# 8335-breakout.net
KiCad netlist of a schematic drawn in EAGLE
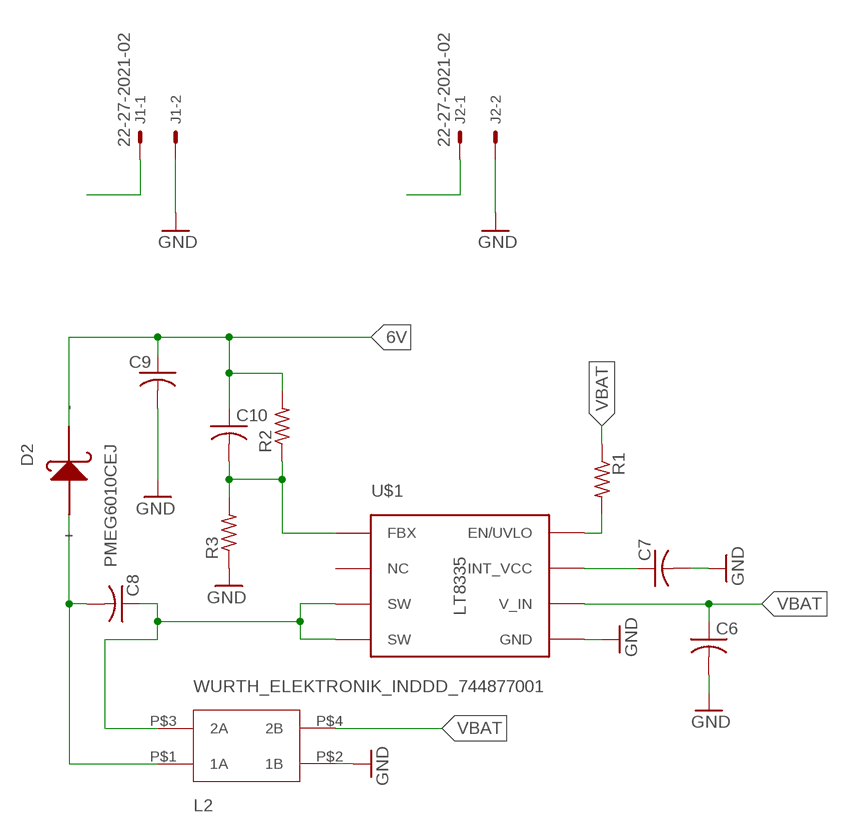
[diagram p0: schematic, sheet 1]

(export (version "E")
  (design (tool "Eeschema 10.0.6"))
  (components
    (comp (ref "C6")
      (value "C-USC0805")
      (footprint "eagle-import:C0805")
      (libsource (lib "eagle-import") (part "C-USC0805"))
    )
    (comp (ref "C7")
      (value "C-USC0805")
      (footprint "eagle-import:C0805")
      (libsource (lib "eagle-import") (part "C-USC0805"))
    )
    (comp (ref "C8")
      (value "C-USC0805")
      (footprint "eagle-import:C0805")
      (libsource (lib "eagle-import") (part "C-USC0805"))
    )
    (comp (ref "C9")
      (value "C-USC0805")
      (footprint "eagle-import:C0805")
      (libsource (lib "eagle-import") (part "C-USC0805"))
    )
    (comp (ref "C10")
      (value "C-USC0805")
      (footprint "eagle-import:C0805")
      (libsource (lib "eagle-import") (part "C-USC0805"))
    )
    (comp (ref "D2")
      (value "PMEG6010CEJ")
      (footprint "eagle-import:SC-90")
      (libsource (lib "eagle-import") (part "PMEG6010CEJ"))
    )
    (comp (ref "J1")
      (value "22-27-2021-02")
      (footprint "eagle-import:6410-02")
      (libsource (lib "eagle-import") (part "22-?-0227-2021"))
    )
    (comp (ref "J2")
      (value "22-27-2021-02")
      (footprint "eagle-import:6410-02")
      (libsource (lib "eagle-import") (part "22-?-0227-2021"))
    )
    (comp (ref "L2")
      (value "WURTH_ELEKTRONIK_INDDD_744877001")
      (footprint "eagle-import:WURTH_ELEKTRONIK_INDDD_744877001")
      (libsource (lib "eagle-import") (part "WURTH_ELEKTRONIK_INDDD_744877001"))
    )
    (comp (ref "R1")
      (value "R-US_R0805")
      (footprint "eagle-import:R0805")
      (libsource (lib "eagle-import") (part "R-US_R0805"))
    )
    (comp (ref "R2")
      (value "R-US_R0805")
      (footprint "eagle-import:R0805")
      (libsource (lib "eagle-import") (part "R-US_R0805"))
    )
    (comp (ref "R3")
      (value "R-US_R0805")
      (footprint "eagle-import:R0805")
      (libsource (lib "eagle-import") (part "R-US_R0805"))
    )
    (comp (ref "U$1")
      (value "LT8335")
      (footprint "eagle-import:DDB")
      (libsource (lib "eagle-import") (part "LT8335"))
    )
  )
  (nets
    (net (code "1") (name "6V") (class "Default")
      (node (ref "C10") (pin "1") (pinfunction "1_1") (pintype "passive"))
      (node (ref "C9") (pin "1") (pinfunction "1_1") (pintype "passive"))
      (node (ref "D2") (pin "P$2") (pinfunction "-_P$2") (pintype "bidirectional"))
      (node (ref "J1") (pin "1") (pinfunction "S_1") (pintype "passive"))
      (node (ref "R2") (pin "2") (pinfunction "2_2") (pintype "passive"))
    )
    (net (code "2") (name "GND") (class "Default")
      (node (ref "C6") (pin "2") (pinfunction "2_2") (pintype "passive"))
      (node (ref "C7") (pin "2") (pinfunction "2_2") (pintype "passive"))
      (node (ref "C9") (pin "2") (pinfunction "2_2") (pintype "passive"))
      (node (ref "J1") (pin "2") (pinfunction "S_2") (pintype "passive"))
      (node (ref "J2") (pin "2") (pinfunction "S_2") (pintype "passive"))
      (node (ref "L2") (pin "P$2") (pinfunction "1B_P$2") (pintype "bidirectional"))
      (node (ref "R3") (pin "1") (pinfunction "1_1") (pintype "passive"))
      (node (ref "U$1") (pin "GND") (pinfunction "GND_GND") (pintype "bidirectional"))
      (node (ref "U$1") (pin "P$5") (pinfunction "GND_P$5") (pintype "bidirectional"))
    )
    (net (code "3") (name "Net-(D2-+)") (class "Default")
      (node (ref "C8") (pin "2") (pinfunction "2_2") (pintype "passive"))
      (node (ref "D2") (pin "P$1") (pinfunction "+_P$1") (pintype "bidirectional"))
      (node (ref "L2") (pin "P$1") (pinfunction "1A_P$1") (pintype "bidirectional"))
    )
    (net (code "4") (name "Net-(L2-2A)") (class "Default")
      (node (ref "C8") (pin "1") (pinfunction "1_1") (pintype "passive"))
      (node (ref "L2") (pin "P$3") (pinfunction "2A_P$3") (pintype "bidirectional"))
      (node (ref "U$1") (pin "P$3") (pinfunction "SW_P$3") (pintype "bidirectional"))
      (node (ref "U$1") (pin "P$4") (pinfunction "SW_P$4") (pintype "bidirectional"))
    )
    (net (code "5") (name "Net-(U$1-EN{slash}UVLO)") (class "Default")
      (node (ref "R1") (pin "2") (pinfunction "2_2") (pintype "passive"))
      (node (ref "U$1") (pin "P$8") (pinfunction "EN/UVLO_P$8") (pintype "bidirectional"))
    )
    (net (code "6") (name "Net-(U$1-FBX)") (class "Default")
      (node (ref "C10") (pin "2") (pinfunction "2_2") (pintype "passive"))
      (node (ref "R2") (pin "1") (pinfunction "1_1") (pintype "passive"))
      (node (ref "R3") (pin "2") (pinfunction "2_2") (pintype "passive"))
      (node (ref "U$1") (pin "P$1") (pinfunction "FBX_P$1") (pintype "bidirectional"))
    )
    (net (code "7") (name "Net-(U$1-INT_VCC)") (class "Default")
      (node (ref "C7") (pin "1") (pinfunction "1_1") (pintype "passive"))
      (node (ref "U$1") (pin "P$7") (pinfunction "INT_VCC_P$7") (pintype "bidirectional"))
    )
    (net (code "8") (name "VBAT") (class "Default")
      (node (ref "C6") (pin "1") (pinfunction "1_1") (pintype "passive"))
      (node (ref "J2") (pin "1") (pinfunction "S_1") (pintype "passive"))
      (node (ref "L2") (pin "P$4") (pinfunction "2B_P$4") (pintype "bidirectional"))
      (node (ref "R1") (pin "1") (pinfunction "1_1") (pintype "passive"))
      (node (ref "U$1") (pin "P$6") (pinfunction "V_IN_P$6") (pintype "bidirectional"))
    )
    (net (code "9") (name "unconnected-(U$1-NC-PadP$2)") (class "Default")
      (node (ref "U$1") (pin "P$2") (pinfunction "NC_P$2") (pintype "bidirectional"))
    )
  )
)
